# flowerfriend_rev6.net
KiCad netlist of a schematic drawn in EAGLE
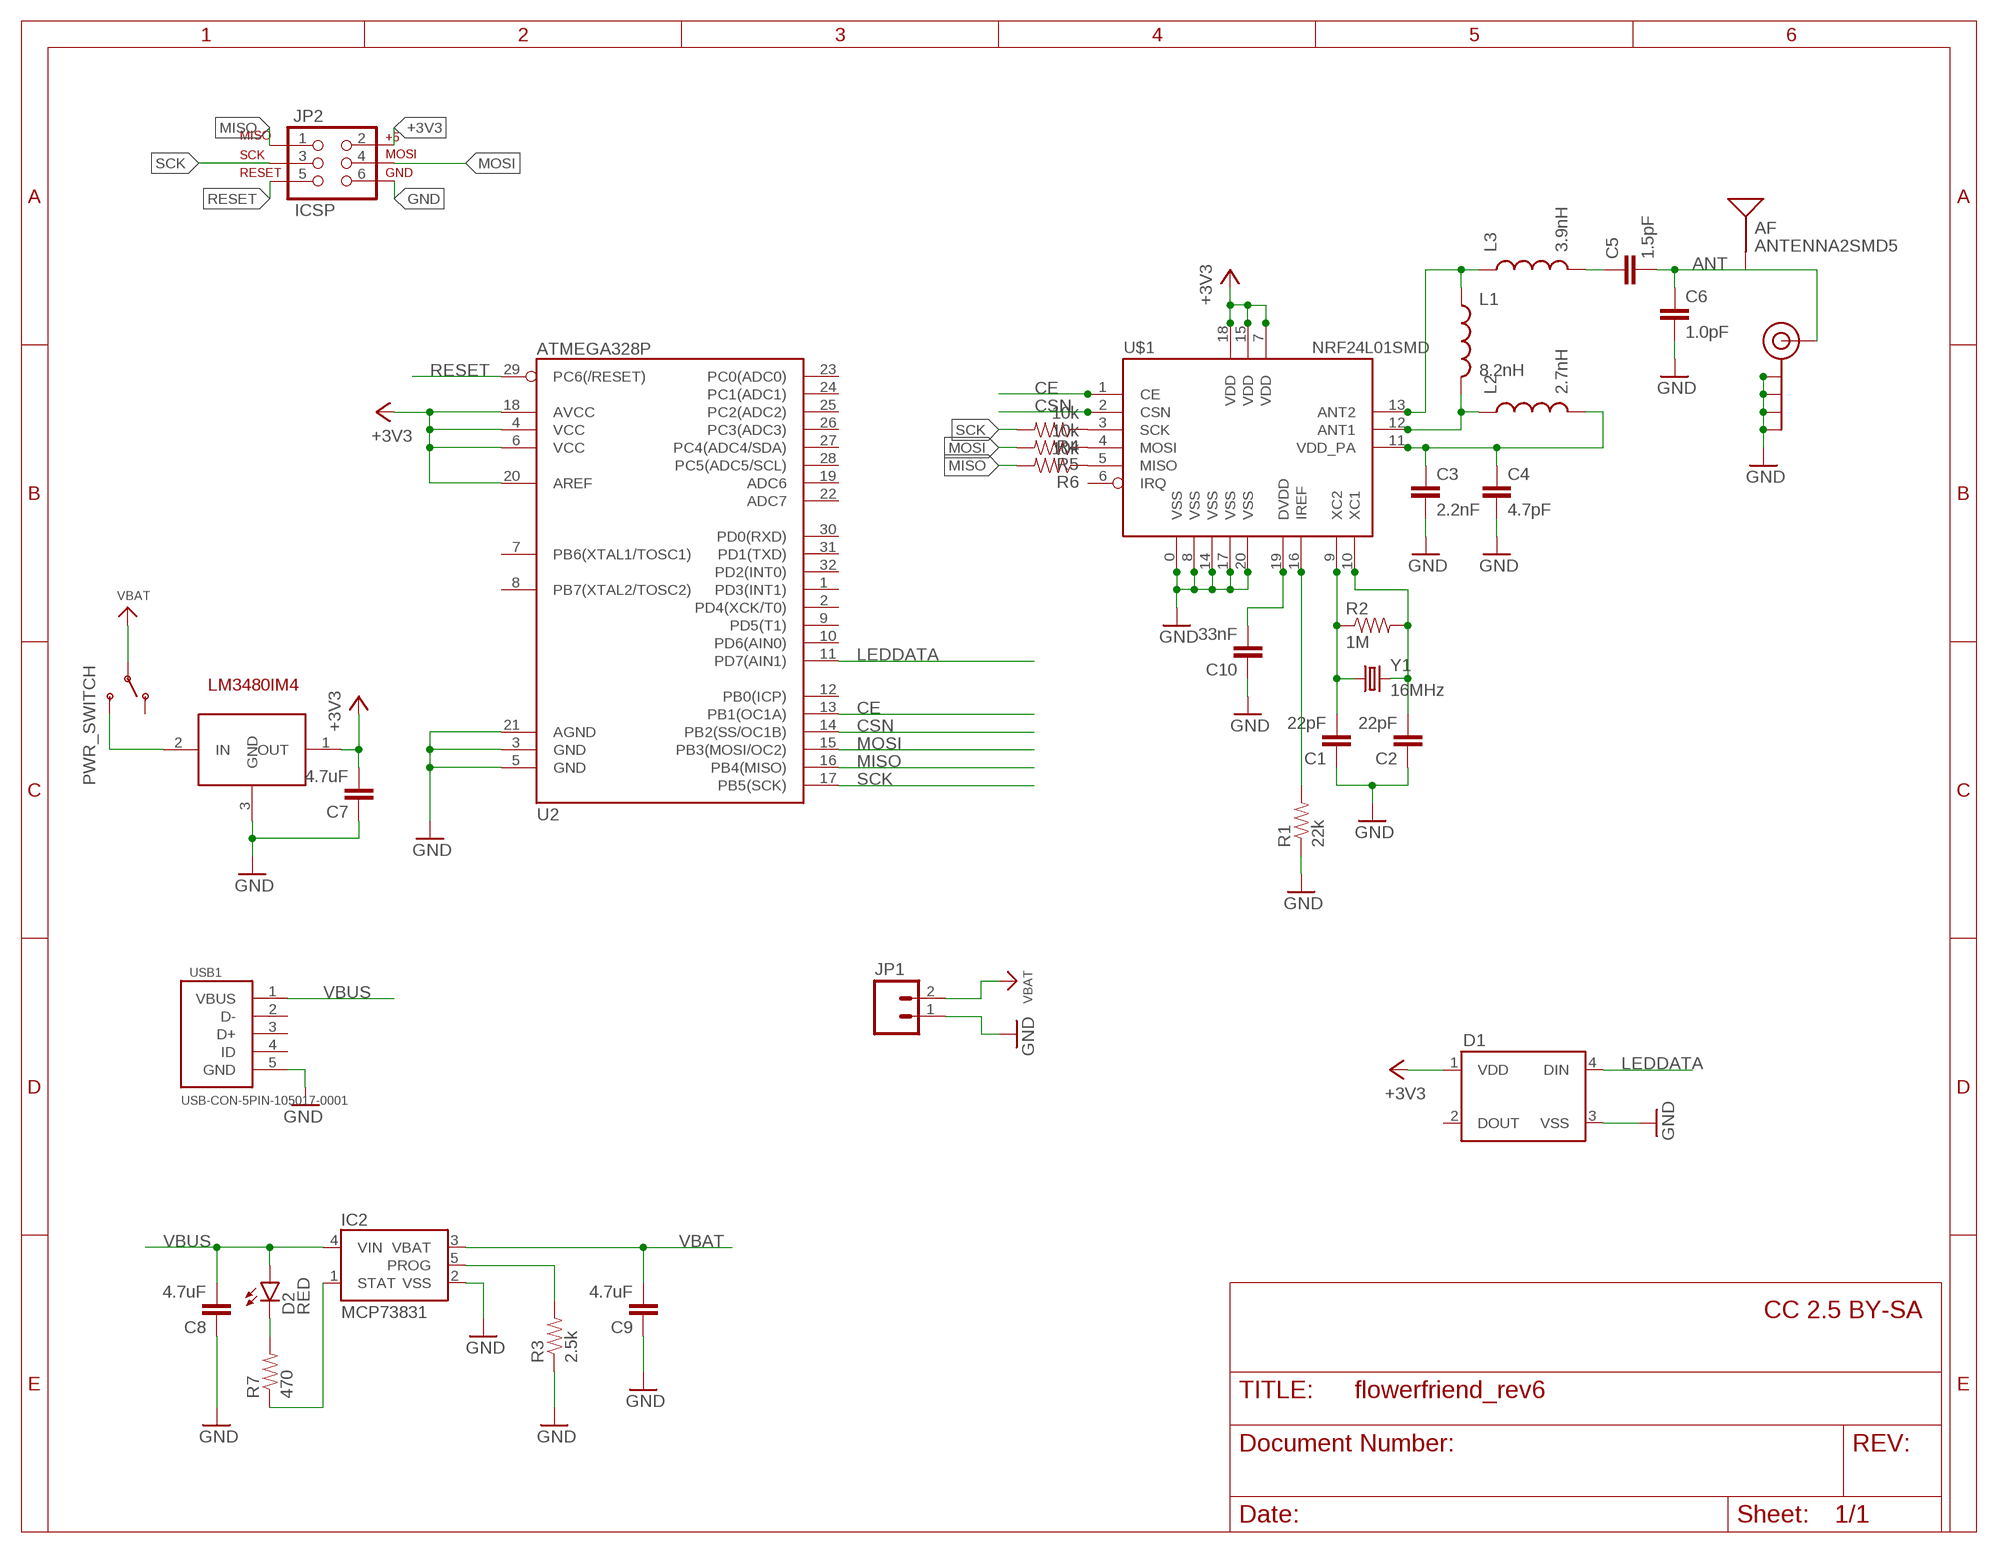
[diagram p0: schematic, sheet 1]

(export (version "E")
  (design (tool "Eeschema 10.0.6"))
  (components
    (comp (ref "AF")
      (value "ANTENNA2SMD5")
      (footprint "eagle-import:ANTENNA-CHIP5")
      (libsource (lib "eagle-import") (part "ANTENNA2SMD5"))
    )
    (comp (ref "C1")
      (value "22pF")
      (footprint "eagle-import:0805")
      (libsource (lib "eagle-import") (part "CAP0805"))
    )
    (comp (ref "C2")
      (value "22pF")
      (footprint "eagle-import:0805")
      (libsource (lib "eagle-import") (part "CAP0805"))
    )
    (comp (ref "C3")
      (value "2.2nF")
      (footprint "eagle-import:C0402")
      (libsource (lib "eagle-import") (part "CAP_C0402"))
    )
    (comp (ref "C4")
      (value "4.7pF")
      (footprint "eagle-import:C0402")
      (libsource (lib "eagle-import") (part "CAP_C0402"))
    )
    (comp (ref "C5")
      (value "1.5pF")
      (footprint "eagle-import:C0402")
      (libsource (lib "eagle-import") (part "CAP_C0402"))
    )
    (comp (ref "C6")
      (value "1.0pF")
      (footprint "eagle-import:C0402")
      (libsource (lib "eagle-import") (part "CAP_C0402"))
    )
    (comp (ref "C7")
      (value "4.7uF")
      (footprint "eagle-import:0805")
      (libsource (lib "eagle-import") (part "CAP0805"))
    )
    (comp (ref "C8")
      (value "4.7uF")
      (footprint "eagle-import:0805")
      (libsource (lib "eagle-import") (part "CAP0805"))
    )
    (comp (ref "C9")
      (value "4.7uF")
      (footprint "eagle-import:0805")
      (libsource (lib "eagle-import") (part "CAP0805"))
    )
    (comp (ref "C10")
      (value "33nF")
      (footprint "eagle-import:0805")
      (libsource (lib "eagle-import") (part "CAP0805"))
    )
    (comp (ref "D1")
      (value "WS2812B")
      (footprint "eagle-import:WS2812B")
      (libsource (lib "eagle-import") (part "WS2812B"))
    )
    (comp (ref "D2")
      (value "RED")
      (footprint "eagle-import:LED-0603")
      (libsource (lib "eagle-import") (part "LED-RED0603"))
    )
    (comp (ref "IC1")
      (value "LM3480IM4")
      (footprint "eagle-import:SOT23-3")
      (libsource (lib "eagle-import") (part "LM3480IM4"))
    )
    (comp (ref "IC2")
      (value "MCP73831")
      (footprint "eagle-import:SOT23-5")
      (libsource (lib "eagle-import") (part "MCP73831"))
    )
    (comp (ref "J$1")
      (value "SMA_EDGE")
      (footprint "eagle-import:SMA-EDGE")
      (libsource (lib "eagle-import") (part "SMA_EDGE"))
    )
    (comp (ref "JP1")
      (value "M02PTH")
      (footprint "eagle-import:1X02")
      (libsource (lib "eagle-import") (part "M02PTH"))
    )
    (comp (ref "JP2")
      (value "ICSP")
      (footprint "eagle-import:2X3")
      (libsource (lib "eagle-import") (part "AVR_SPI_PRG_6PTH"))
    )
    (comp (ref "L1")
      (value "8.2nH")
      (footprint "eagle-import:C0402")
      (libsource (lib "eagle-import") (part "INDUCTOR0402"))
    )
    (comp (ref "L2")
      (value "2.7nH")
      (footprint "eagle-import:C0402")
      (libsource (lib "eagle-import") (part "INDUCTOR0402"))
    )
    (comp (ref "L3")
      (value "3.9nH")
      (footprint "eagle-import:C0402")
      (libsource (lib "eagle-import") (part "INDUCTOR0402"))
    )
    (comp (ref "PWR_SWITCH")
      (value "SWITCH_SPDT")
      (footprint "eagle-import:KPS-1290")
      (libsource (lib "eagle-import") (part "SWITCH_SPDT"))
    )
    (comp (ref "R1")
      (value "22k")
      (footprint "eagle-import:0805")
      (libsource (lib "eagle-import") (part "RESISTOR0805-RES"))
    )
    (comp (ref "R2")
      (value "1M")
      (footprint "eagle-import:0805")
      (libsource (lib "eagle-import") (part "RESISTOR0805-RES"))
    )
    (comp (ref "R3")
      (value "2.5k")
      (footprint "eagle-import:0805")
      (libsource (lib "eagle-import") (part "RESISTOR0805-RES"))
    )
    (comp (ref "R4")
      (value "10k")
      (footprint "eagle-import:0805")
      (libsource (lib "eagle-import") (part "RESISTOR0805-RES"))
    )
    (comp (ref "R5")
      (value "10k")
      (footprint "eagle-import:0805")
      (libsource (lib "eagle-import") (part "RESISTOR0805-RES"))
    )
    (comp (ref "R6")
      (value "10k")
      (footprint "eagle-import:0805")
      (libsource (lib "eagle-import") (part "RESISTOR0805-RES"))
    )
    (comp (ref "R7")
      (value "470")
      (footprint "eagle-import:0805")
      (libsource (lib "eagle-import") (part "RESISTOR0805-RES"))
    )
    (comp (ref "U$1")
      (value "NRF24L01SMD")
      (footprint "eagle-import:QFN20")
      (libsource (lib "eagle-import") (part "NRF24L01SMD"))
    )
    (comp (ref "U2")
      (value "ATMEGA328P")
      (footprint "eagle-import:TQFP32-08")
      (libsource (lib "eagle-import") (part "ATMEGA328_SMT"))
    )
    (comp (ref "USB1")
      (value "USB-CON-5PIN-105017-0001")
      (footprint "eagle-import:USB-MICRO-MOLEX-105017-0001")
      (libsource (lib "eagle-import") (part "USB-CON-5PIN-105017-0001"))
    )
    (comp (ref "Y1")
      (value "16MHz")
      (footprint "eagle-import:CRYSTAL-SMD-5X3")
      (libsource (lib "eagle-import") (part "CRYSTAL5X3"))
    )
  )
  (nets
    (net (code "1") (name "+3V3") (class "Default")
      (node (ref "C7") (pin "2") (pinfunction "2_2") (pintype "passive"))
      (node (ref "D1") (pin "1") (pinfunction "VDD_1") (pintype "power_in"))
      (node (ref "IC1") (pin "1") (pinfunction "OUT_1") (pintype "bidirectional"))
      (node (ref "JP2") (pin "2") (pinfunction "2_2") (pintype "passive"))
      (node (ref "U$1") (pin "15") (pinfunction "VDD_15") (pintype "power_in"))
      (node (ref "U$1") (pin "18") (pinfunction "VDD_18") (pintype "power_in"))
      (node (ref "U$1") (pin "7") (pinfunction "VDD_7") (pintype "power_in"))
      (node (ref "U2") (pin "18") (pinfunction "AVCC_18") (pintype "bidirectional"))
      (node (ref "U2") (pin "20") (pinfunction "AREF_20") (pintype "bidirectional"))
      (node (ref "U2") (pin "4") (pinfunction "VCC_4") (pintype "bidirectional"))
      (node (ref "U2") (pin "6") (pinfunction "VCC_6") (pintype "bidirectional"))
    )
    (net (code "2") (name "/ANT") (class "Default")
      (node (ref "AF") (pin "FEED") (pinfunction "SIGNAL_FEED") (pintype "bidirectional"))
      (node (ref "C5") (pin "2") (pinfunction "2_2") (pintype "passive"))
      (node (ref "C6") (pin "1") (pinfunction "1_1") (pintype "passive"))
      (node (ref "J$1") (pin "SIG") (pinfunction "SIGNAL_SIG") (pintype "bidirectional"))
    )
    (net (code "3") (name "/CE") (class "Default")
      (node (ref "U$1") (pin "1") (pinfunction "CE_1") (pintype "input"))
      (node (ref "U2") (pin "13") (pinfunction "PB1(OC1A)_13") (pintype "bidirectional"))
    )
    (net (code "4") (name "/CSN") (class "Default")
      (node (ref "U$1") (pin "2") (pinfunction "CSN_2") (pintype "input"))
      (node (ref "U2") (pin "14") (pinfunction "PB2(SS/OC1B)_14") (pintype "bidirectional"))
    )
    (net (code "5") (name "/LEDDATA") (class "Default")
      (node (ref "D1") (pin "4") (pinfunction "DIN_4") (pintype "input"))
      (node (ref "U2") (pin "11") (pinfunction "PD7(AIN1)_11") (pintype "bidirectional"))
    )
    (net (code "6") (name "/VBUS") (class "Default")
      (node (ref "C8") (pin "2") (pinfunction "2_2") (pintype "passive"))
      (node (ref "D2") (pin "A") (pinfunction "A_A") (pintype "passive"))
      (node (ref "IC2") (pin "4") (pinfunction "VIN_4") (pintype "power_in"))
      (node (ref "USB1") (pin "1") (pinfunction "VBUS_1") (pintype "power_in"))
    )
    (net (code "7") (name "GND") (class "Default")
      (node (ref "C1") (pin "1") (pinfunction "1_1") (pintype "passive"))
      (node (ref "C10") (pin "1") (pinfunction "1_1") (pintype "passive"))
      (node (ref "C2") (pin "1") (pinfunction "1_1") (pintype "passive"))
      (node (ref "C3") (pin "2") (pinfunction "2_2") (pintype "passive"))
      (node (ref "C4") (pin "2") (pinfunction "2_2") (pintype "passive"))
      (node (ref "C6") (pin "2") (pinfunction "2_2") (pintype "passive"))
      (node (ref "C7") (pin "1") (pinfunction "1_1") (pintype "passive"))
      (node (ref "C8") (pin "1") (pinfunction "1_1") (pintype "passive"))
      (node (ref "C9") (pin "1") (pinfunction "1_1") (pintype "passive"))
      (node (ref "D1") (pin "3") (pinfunction "VSS_3") (pintype "power_in"))
      (node (ref "IC1") (pin "3") (pinfunction "GND_3") (pintype "bidirectional"))
      (node (ref "IC2") (pin "2") (pinfunction "VSS_2") (pintype "power_in"))
      (node (ref "J$1") (pin "GND@0") (pinfunction "GND_GND@0") (pintype "bidirectional"))
      (node (ref "J$1") (pin "GND@1") (pinfunction "GND_GND@1") (pintype "bidirectional"))
      (node (ref "J$1") (pin "GND@2") (pinfunction "GND_GND@2") (pintype "bidirectional"))
      (node (ref "J$1") (pin "GND@3") (pinfunction "GND_GND@3") (pintype "bidirectional"))
      (node (ref "JP1") (pin "1") (pinfunction "1_1") (pintype "passive"))
      (node (ref "JP2") (pin "6") (pinfunction "6_6") (pintype "passive"))
      (node (ref "R1") (pin "1") (pinfunction "1_1") (pintype "passive"))
      (node (ref "R3") (pin "1") (pinfunction "1_1") (pintype "passive"))
      (node (ref "U$1") (pin "0") (pinfunction "VSS_0") (pintype "power_in"))
      (node (ref "U$1") (pin "14") (pinfunction "VSS_14") (pintype "power_in"))
      (node (ref "U$1") (pin "17") (pinfunction "VSS_17") (pintype "power_in"))
      (node (ref "U$1") (pin "20") (pinfunction "VSS_20") (pintype "power_in"))
      (node (ref "U$1") (pin "8") (pinfunction "VSS_8") (pintype "power_in"))
      (node (ref "U2") (pin "21") (pinfunction "AGND_21") (pintype "bidirectional"))
      (node (ref "U2") (pin "3") (pinfunction "GND_3") (pintype "bidirectional"))
      (node (ref "U2") (pin "5") (pinfunction "GND_5") (pintype "bidirectional"))
      (node (ref "USB1") (pin "5") (pinfunction "GND_5") (pintype "power_in"))
    )
    (net (code "8") (name "MISO") (class "Default")
      (node (ref "JP2") (pin "1") (pinfunction "1_1") (pintype "passive"))
      (node (ref "R6") (pin "2") (pinfunction "2_2") (pintype "passive"))
      (node (ref "U2") (pin "16") (pinfunction "PB4(MISO)_16") (pintype "bidirectional"))
    )
    (net (code "9") (name "MOSI") (class "Default")
      (node (ref "JP2") (pin "4") (pinfunction "4_4") (pintype "passive"))
      (node (ref "R5") (pin "2") (pinfunction "2_2") (pintype "passive"))
      (node (ref "U2") (pin "15") (pinfunction "PB3(MOSI/OC2)_15") (pintype "bidirectional"))
    )
    (net (code "10") (name "Net-(C5-Pad1)") (class "Default")
      (node (ref "C5") (pin "1") (pinfunction "1_1") (pintype "passive"))
      (node (ref "L3") (pin "2") (pinfunction "2_2") (pintype "passive"))
    )
    (net (code "11") (name "Net-(D2-PadC)") (class "Default")
      (node (ref "D2") (pin "C") (pinfunction "C_C") (pintype "passive"))
      (node (ref "R7") (pin "2") (pinfunction "2_2") (pintype "passive"))
    )
    (net (code "12") (name "Net-(IC1-IN)") (class "Default")
      (node (ref "IC1") (pin "2") (pinfunction "IN_2") (pintype "bidirectional"))
      (node (ref "PWR_SWITCH") (pin "S") (pinfunction "S_S") (pintype "passive"))
    )
    (net (code "13") (name "Net-(IC2-PROG)") (class "Default")
      (node (ref "IC2") (pin "5") (pinfunction "PROG_5") (pintype "input"))
      (node (ref "R3") (pin "2") (pinfunction "2_2") (pintype "passive"))
    )
    (net (code "14") (name "Net-(IC2-STAT)") (class "Default")
      (node (ref "IC2") (pin "1") (pinfunction "STAT_1") (pintype "output"))
      (node (ref "R7") (pin "1") (pinfunction "1_1") (pintype "passive"))
    )
    (net (code "15") (name "Net-(U$1-ANT1)") (class "Default")
      (node (ref "L1") (pin "2") (pinfunction "2_2") (pintype "passive"))
      (node (ref "L2") (pin "1") (pinfunction "1_1") (pintype "passive"))
      (node (ref "U$1") (pin "12") (pinfunction "ANT1_12") (pintype "output"))
    )
    (net (code "16") (name "Net-(U$1-ANT2)") (class "Default")
      (node (ref "L1") (pin "1") (pinfunction "1_1") (pintype "passive"))
      (node (ref "L3") (pin "1") (pinfunction "1_1") (pintype "passive"))
      (node (ref "U$1") (pin "13") (pinfunction "ANT2_13") (pintype "output"))
    )
    (net (code "17") (name "Net-(U$1-DVDD)") (class "Default")
      (node (ref "C10") (pin "2") (pinfunction "2_2") (pintype "passive"))
      (node (ref "U$1") (pin "19") (pinfunction "DVDD_19") (pintype "power_in"))
    )
    (net (code "18") (name "Net-(U$1-IREF)") (class "Default")
      (node (ref "R1") (pin "2") (pinfunction "2_2") (pintype "passive"))
      (node (ref "U$1") (pin "16") (pinfunction "IREF_16") (pintype "input"))
    )
    (net (code "19") (name "Net-(U$1-MISO)") (class "Default")
      (node (ref "R6") (pin "1") (pinfunction "1_1") (pintype "passive"))
      (node (ref "U$1") (pin "5") (pinfunction "MISO_5") (pintype "output"))
    )
    (net (code "20") (name "Net-(U$1-MOSI)") (class "Default")
      (node (ref "R5") (pin "1") (pinfunction "1_1") (pintype "passive"))
      (node (ref "U$1") (pin "4") (pinfunction "MOSI_4") (pintype "input"))
    )
    (net (code "21") (name "Net-(U$1-SCK)") (class "Default")
      (node (ref "R4") (pin "1") (pinfunction "1_1") (pintype "passive"))
      (node (ref "U$1") (pin "3") (pinfunction "SCK_3") (pintype "input"))
    )
    (net (code "22") (name "Net-(U$1-VDD_PA)") (class "Default")
      (node (ref "C3") (pin "1") (pinfunction "1_1") (pintype "passive"))
      (node (ref "C4") (pin "1") (pinfunction "1_1") (pintype "passive"))
      (node (ref "L2") (pin "2") (pinfunction "2_2") (pintype "passive"))
      (node (ref "U$1") (pin "11") (pinfunction "VDD_PA_11") (pintype "power_in"))
    )
    (net (code "23") (name "Net-(U$1-XC1)") (class "Default")
      (node (ref "C2") (pin "2") (pinfunction "2_2") (pintype "passive"))
      (node (ref "R2") (pin "2") (pinfunction "2_2") (pintype "passive"))
      (node (ref "U$1") (pin "10") (pinfunction "XC1_10") (pintype "input"))
      (node (ref "Y1") (pin "3") (pinfunction "2_3") (pintype "passive"))
    )
    (net (code "24") (name "Net-(U$1-XC2)") (class "Default")
      (node (ref "C1") (pin "2") (pinfunction "2_2") (pintype "passive"))
      (node (ref "R2") (pin "1") (pinfunction "1_1") (pintype "passive"))
      (node (ref "U$1") (pin "9") (pinfunction "XC2_9") (pintype "input"))
      (node (ref "Y1") (pin "1") (pinfunction "1_1") (pintype "passive"))
    )
    (net (code "25") (name "RESET") (class "Default")
      (node (ref "JP2") (pin "5") (pinfunction "5_5") (pintype "passive"))
      (node (ref "U2") (pin "29") (pinfunction "PC6(/RESET)_29") (pintype "bidirectional"))
    )
    (net (code "26") (name "SCK") (class "Default")
      (node (ref "JP2") (pin "3") (pinfunction "3_3") (pintype "passive"))
      (node (ref "R4") (pin "2") (pinfunction "2_2") (pintype "passive"))
      (node (ref "U2") (pin "17") (pinfunction "PB5(SCK)_17") (pintype "bidirectional"))
    )
    (net (code "27") (name "VBAT") (class "Default")
      (node (ref "C9") (pin "2") (pinfunction "2_2") (pintype "passive"))
      (node (ref "IC2") (pin "3") (pinfunction "VBAT_3") (pintype "power_in"))
      (node (ref "JP1") (pin "2") (pinfunction "2_2") (pintype "passive"))
      (node (ref "PWR_SWITCH") (pin "P") (pinfunction "P_P") (pintype "passive"))
    )
    (net (code "28") (name "unconnected-(D1-DOUT-Pad2)") (class "Default")
      (node (ref "D1") (pin "2") (pinfunction "DOUT_2") (pintype "output"))
    )
    (net (code "29") (name "unconnected-(PWR_SWITCH-PadO)") (class "Default")
      (node (ref "PWR_SWITCH") (pin "O") (pinfunction "O_O") (pintype "passive"))
    )
    (net (code "30") (name "unconnected-(U$1-IRQ-Pad6)") (class "Default")
      (node (ref "U$1") (pin "6") (pinfunction "IRQ_6") (pintype "output"))
    )
    (net (code "31") (name "unconnected-(U2-ADC6-Pad19)") (class "Default")
      (node (ref "U2") (pin "19") (pinfunction "ADC6_19") (pintype "bidirectional"))
    )
    (net (code "32") (name "unconnected-(U2-ADC7-Pad22)") (class "Default")
      (node (ref "U2") (pin "22") (pinfunction "ADC7_22") (pintype "bidirectional"))
    )
    (net (code "33") (name "unconnected-(U2-PB0(ICP)-Pad12)") (class "Default")
      (node (ref "U2") (pin "12") (pinfunction "PB0(ICP)_12") (pintype "bidirectional"))
    )
    (net (code "34") (name "unconnected-(U2-PB6(XTAL1{slash}TOSC1)-Pad7)") (class "Default")
      (node (ref "U2") (pin "7") (pinfunction "PB6(XTAL1/TOSC1)_7") (pintype "bidirectional"))
    )
    (net (code "35") (name "unconnected-(U2-PB7(XTAL2{slash}TOSC2)-Pad8)") (class "Default")
      (node (ref "U2") (pin "8") (pinfunction "PB7(XTAL2/TOSC2)_8") (pintype "bidirectional"))
    )
    (net (code "36") (name "unconnected-(U2-PC0(ADC0)-Pad23)") (class "Default")
      (node (ref "U2") (pin "23") (pinfunction "PC0(ADC0)_23") (pintype "bidirectional"))
    )
    (net (code "37") (name "unconnected-(U2-PC1(ADC1)-Pad24)") (class "Default")
      (node (ref "U2") (pin "24") (pinfunction "PC1(ADC1)_24") (pintype "bidirectional"))
    )
    (net (code "38") (name "unconnected-(U2-PC2(ADC2)-Pad25)") (class "Default")
      (node (ref "U2") (pin "25") (pinfunction "PC2(ADC2)_25") (pintype "bidirectional"))
    )
    (net (code "39") (name "unconnected-(U2-PC3(ADC3)-Pad26)") (class "Default")
      (node (ref "U2") (pin "26") (pinfunction "PC3(ADC3)_26") (pintype "bidirectional"))
    )
    (net (code "40") (name "unconnected-(U2-PC4(ADC4{slash}SDA)-Pad27)") (class "Default")
      (node (ref "U2") (pin "27") (pinfunction "PC4(ADC4/SDA)_27") (pintype "bidirectional"))
    )
    (net (code "41") (name "unconnected-(U2-PC5(ADC5{slash}SCL)-Pad28)") (class "Default")
      (node (ref "U2") (pin "28") (pinfunction "PC5(ADC5/SCL)_28") (pintype "bidirectional"))
    )
    (net (code "42") (name "unconnected-(U2-PD0(RXD)-Pad30)") (class "Default")
      (node (ref "U2") (pin "30") (pinfunction "PD0(RXD)_30") (pintype "bidirectional"))
    )
    (net (code "43") (name "unconnected-(U2-PD1(TXD)-Pad31)") (class "Default")
      (node (ref "U2") (pin "31") (pinfunction "PD1(TXD)_31") (pintype "bidirectional"))
    )
    (net (code "44") (name "unconnected-(U2-PD2(INT0)-Pad32)") (class "Default")
      (node (ref "U2") (pin "32") (pinfunction "PD2(INT0)_32") (pintype "bidirectional"))
    )
    (net (code "45") (name "unconnected-(U2-PD3(INT1)-Pad1)") (class "Default")
      (node (ref "U2") (pin "1") (pinfunction "PD3(INT1)_1") (pintype "bidirectional"))
    )
    (net (code "46") (name "unconnected-(U2-PD4(XCK{slash}T0)-Pad2)") (class "Default")
      (node (ref "U2") (pin "2") (pinfunction "PD4(XCK/T0)_2") (pintype "bidirectional"))
    )
    (net (code "47") (name "unconnected-(U2-PD5(T1)-Pad9)") (class "Default")
      (node (ref "U2") (pin "9") (pinfunction "PD5(T1)_9") (pintype "bidirectional"))
    )
    (net (code "48") (name "unconnected-(U2-PD6(AIN0)-Pad10)") (class "Default")
      (node (ref "U2") (pin "10") (pinfunction "PD6(AIN0)_10") (pintype "bidirectional"))
    )
    (net (code "49") (name "unconnected-(USB1-D+-Pad3)") (class "Default")
      (node (ref "USB1") (pin "3") (pinfunction "D+_3") (pintype "bidirectional"))
    )
    (net (code "50") (name "unconnected-(USB1-D--Pad2)") (class "Default")
      (node (ref "USB1") (pin "2") (pinfunction "D-_2") (pintype "bidirectional"))
    )
    (net (code "51") (name "unconnected-(USB1-ID-Pad4)") (class "Default")
      (node (ref "USB1") (pin "4") (pinfunction "ID_4") (pintype "bidirectional"))
    )
  )
)
